# LedController.net
KiCad netlist of a schematic drawn in EAGLE
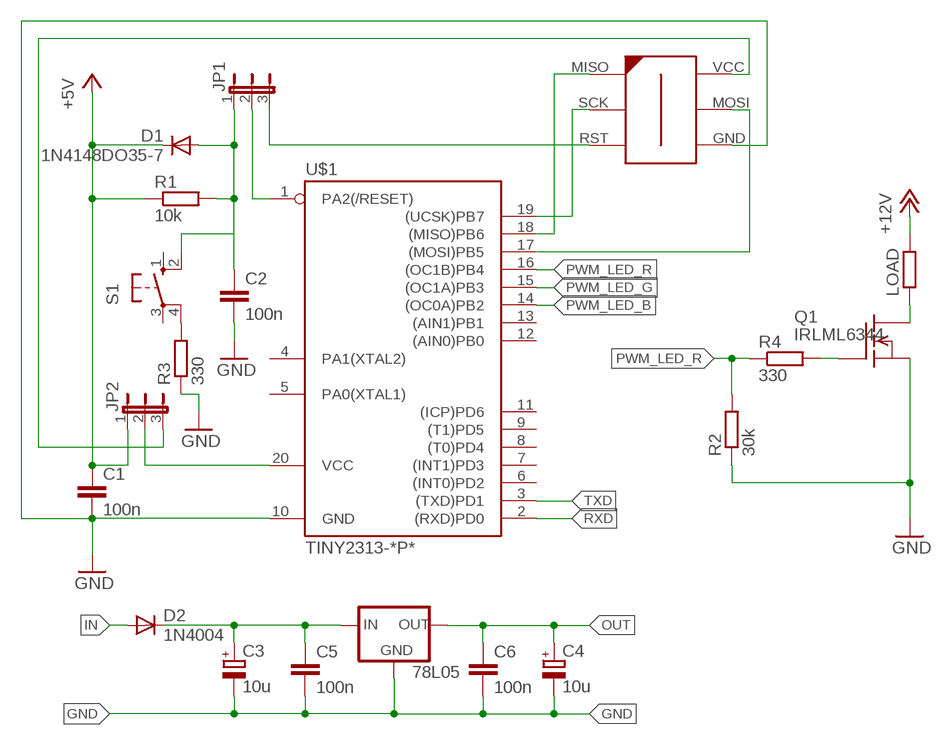
[diagram p0: schematic, sheet 1]

(export (version "E")
  (design (tool "Eeschema 10.0.6"))
  (components
    (comp (ref "78L05")
      (value "78LXX")
      (footprint "eagle-import:78LXX")
      (libsource (lib "eagle-import") (part "78LXX"))
    )
    (comp (ref "C1")
      (value "100n")
      (footprint "eagle-import:C025-024X044")
      (libsource (lib "eagle-import") (part "C-EU025-024X044"))
    )
    (comp (ref "C2")
      (value "100n")
      (footprint "eagle-import:C025-024X044")
      (libsource (lib "eagle-import") (part "C-EU025-024X044"))
    )
    (comp (ref "C3")
      (value "10u")
      (footprint "eagle-import:PANASONIC_A")
      (libsource (lib "eagle-import") (part "CPOL-EUA"))
    )
    (comp (ref "C4")
      (value "10u")
      (footprint "eagle-import:PANASONIC_A")
      (libsource (lib "eagle-import") (part "CPOL-EUA"))
    )
    (comp (ref "C5")
      (value "100n")
      (footprint "eagle-import:C075-032X103")
      (libsource (lib "eagle-import") (part "C-EU075-032X103"))
    )
    (comp (ref "C6")
      (value "100n")
      (footprint "eagle-import:C075-032X103")
      (libsource (lib "eagle-import") (part "C-EU075-032X103"))
    )
    (comp (ref "D1")
      (value "1N4148DO35-7")
      (footprint "eagle-import:DO35-7")
      (libsource (lib "eagle-import") (part "1N4148DO35-7"))
    )
    (comp (ref "D2")
      (value "1N4004")
      (footprint "eagle-import:DO41-10")
      (libsource (lib "eagle-import") (part "1N4004"))
    )
    (comp (ref "JP1")
      (value "JP2E")
      (footprint "eagle-import:JP2")
      (libsource (lib "eagle-import") (part "JP2E"))
    )
    (comp (ref "JP2")
      (value "JP2E")
      (footprint "eagle-import:JP2")
      (libsource (lib "eagle-import") (part "JP2E"))
    )
    (comp (ref "LOAD")
      (value "R-EU_0204/2V")
      (footprint "eagle-import:0204V")
      (libsource (lib "eagle-import") (part "R-EU_0204/2V"))
    )
    (comp (ref "Q1")
      (value "IRLML6344")
      (footprint "eagle-import:TO92")
      (libsource (lib "eagle-import") (part "BSS101"))
    )
    (comp (ref "R1")
      (value "10k")
      (footprint "eagle-import:0204V")
      (libsource (lib "eagle-import") (part "R-EU_0204/2V"))
    )
    (comp (ref "R2")
      (value "30k")
      (footprint "eagle-import:0204V")
      (libsource (lib "eagle-import") (part "R-EU_0204/2V"))
    )
    (comp (ref "R3")
      (value "330")
      (footprint "eagle-import:0204V")
      (libsource (lib "eagle-import") (part "R-EU_0204/2V"))
    )
    (comp (ref "R4")
      (value "330")
      (footprint "eagle-import:0204V")
      (libsource (lib "eagle-import") (part "resistor_R-EU_0204/2V"))
    )
    (comp (ref "S1")
      (value "10-XX")
      (footprint "eagle-import:B3F-10XX")
      (fields (field (name "MPN") "B3F-1000"))
      (libsource (lib "eagle-import") (part "10-XX"))
    )
    (comp (ref "U$1")
      (value "TINY2313-*P*")
      (footprint "eagle-import:DIL20")
      (libsource (lib "eagle-import") (part "TINY2313-P"))
    )
    (comp (ref "U$2")
      (value "AVR-ISP-6-EDGE")
      (footprint "eagle-import:6PAD_ISP")
      (libsource (lib "eagle-import") (part "AVR-ISP-6-EDGE"))
    )
  )
  (nets
    (net (code "1") (name "+5V") (class "Default")
      (node (ref "C1") (pin "1") (pinfunction "1_1") (pintype "passive"))
      (node (ref "D1") (pin "C") (pinfunction "C_C") (pintype "passive"))
      (node (ref "JP2") (pin "1") (pinfunction "1_1") (pintype "passive"))
      (node (ref "R1") (pin "1") (pinfunction "1_1") (pintype "passive"))
    )
    (net (code "2") (name "+12V") (class "Default")
      (node (ref "LOAD") (pin "2") (pinfunction "2_2") (pintype "passive"))
    )
    (net (code "3") (name "GND") (class "Default")
      (node (ref "78L05") (pin "GND") (pinfunction "GND_GND") (pintype "input"))
      (node (ref "C1") (pin "2") (pinfunction "2_2") (pintype "passive"))
      (node (ref "C2") (pin "2") (pinfunction "2_2") (pintype "passive"))
      (node (ref "C3") (pin "-") (pinfunction "-_-") (pintype "passive"))
      (node (ref "C4") (pin "-") (pinfunction "-_-") (pintype "passive"))
      (node (ref "C5") (pin "2") (pinfunction "2_2") (pintype "passive"))
      (node (ref "C6") (pin "2") (pinfunction "2_2") (pintype "passive"))
      (node (ref "Q1") (pin "1") (pinfunction "S_1") (pintype "passive"))
      (node (ref "R2") (pin "1") (pinfunction "1_1") (pintype "passive"))
      (node (ref "R3") (pin "1") (pinfunction "1_1") (pintype "passive"))
      (node (ref "U$1") (pin "10") (pinfunction "GND_10") (pintype "power_in"))
      (node (ref "U$2") (pin "GND") (pinfunction "P$4_GND") (pintype "bidirectional"))
    )
    (net (code "4") (name "IN") (class "Default")
      (node (ref "D2") (pin "A") (pinfunction "A_A") (pintype "passive"))
    )
    (net (code "5") (name "Net-(78L05-PadIN)") (class "Default")
      (node (ref "78L05") (pin "IN") (pinfunction "IN_IN") (pintype "input"))
      (node (ref "C3") (pin "+") (pinfunction "+_+") (pintype "passive"))
      (node (ref "C5") (pin "1") (pinfunction "1_1") (pintype "passive"))
      (node (ref "D2") (pin "C") (pinfunction "C_C") (pintype "passive"))
    )
    (net (code "6") (name "Net-(Q1-D)") (class "Default")
      (node (ref "LOAD") (pin "1") (pinfunction "1_1") (pintype "passive"))
      (node (ref "Q1") (pin "3") (pinfunction "D_3") (pintype "passive"))
    )
    (net (code "7") (name "Net-(Q1-G)") (class "Default")
      (node (ref "Q1") (pin "2") (pinfunction "G_2") (pintype "passive"))
      (node (ref "R4") (pin "2") (pinfunction "2_2") (pintype "passive"))
    )
    (net (code "8") (name "Net-(S1-P1)") (class "Default")
      (node (ref "R3") (pin "2") (pinfunction "2_2") (pintype "passive"))
      (node (ref "S1") (pin "4") (pinfunction "P1_4") (pintype "passive"))
    )
    (net (code "9") (name "Net-(S1-S1)") (class "Default")
      (node (ref "C2") (pin "1") (pinfunction "1_1") (pintype "passive"))
      (node (ref "D1") (pin "A") (pinfunction "A_A") (pintype "passive"))
      (node (ref "JP1") (pin "1") (pinfunction "1_1") (pintype "passive"))
      (node (ref "R1") (pin "2") (pinfunction "2_2") (pintype "passive"))
      (node (ref "S1") (pin "2") (pinfunction "S1_2") (pintype "passive"))
    )
    (net (code "10") (name "Net-(U$1-(MISO)PB6)") (class "Default")
      (node (ref "U$1") (pin "18") (pinfunction "(MISO)PB6_18") (pintype "bidirectional"))
      (node (ref "U$2") (pin "MISO") (pinfunction "P$1_MISO") (pintype "bidirectional"))
    )
    (net (code "11") (name "Net-(U$1-(MOSI)PB5)") (class "Default")
      (node (ref "U$1") (pin "17") (pinfunction "(MOSI)PB5_17") (pintype "bidirectional"))
      (node (ref "U$2") (pin "MOSI") (pinfunction "P$5_MOSI") (pintype "bidirectional"))
    )
    (net (code "12") (name "Net-(U$1-(UCSK)PB7)") (class "Default")
      (node (ref "U$1") (pin "19") (pinfunction "(UCSK)PB7_19") (pintype "bidirectional"))
      (node (ref "U$2") (pin "SCK") (pinfunction "P$2_SCK") (pintype "bidirectional"))
    )
    (net (code "13") (name "Net-(U$1-PA2({slash}RESET))") (class "Default")
      (node (ref "JP1") (pin "2") (pinfunction "2_2") (pintype "passive"))
      (node (ref "U$1") (pin "1") (pinfunction "PA2(/RESET)_1") (pintype "input"))
    )
    (net (code "14") (name "Net-(U$1-VCC)") (class "Default")
      (node (ref "JP2") (pin "2") (pinfunction "2_2") (pintype "passive"))
      (node (ref "U$1") (pin "20") (pinfunction "VCC_20") (pintype "power_in"))
    )
    (net (code "15") (name "Net-(U$2-P$3)") (class "Default")
      (node (ref "JP1") (pin "3") (pinfunction "3_3") (pintype "passive"))
      (node (ref "U$2") (pin "RST") (pinfunction "P$3_RST") (pintype "bidirectional"))
    )
    (net (code "16") (name "Net-(U$2-P$6)") (class "Default")
      (node (ref "JP2") (pin "3") (pinfunction "3_3") (pintype "passive"))
      (node (ref "U$2") (pin "VCC") (pinfunction "P$6_VCC") (pintype "bidirectional"))
    )
    (net (code "17") (name "OUT") (class "Default")
      (node (ref "78L05") (pin "OUT") (pinfunction "OUT_OUT") (pintype "passive"))
      (node (ref "C4") (pin "+") (pinfunction "+_+") (pintype "passive"))
      (node (ref "C6") (pin "1") (pinfunction "1_1") (pintype "passive"))
    )
    (net (code "18") (name "PWM_LED_B") (class "Default")
      (node (ref "U$1") (pin "14") (pinfunction "(OC0A)PB2_14") (pintype "bidirectional"))
    )
    (net (code "19") (name "PWM_LED_G") (class "Default")
      (node (ref "U$1") (pin "15") (pinfunction "(OC1A)PB3_15") (pintype "bidirectional"))
    )
    (net (code "20") (name "PWM_LED_R") (class "Default")
      (node (ref "R2") (pin "2") (pinfunction "2_2") (pintype "passive"))
      (node (ref "R4") (pin "1") (pinfunction "1_1") (pintype "passive"))
      (node (ref "U$1") (pin "16") (pinfunction "(OC1B)PB4_16") (pintype "bidirectional"))
    )
    (net (code "21") (name "RXD") (class "Default")
      (node (ref "U$1") (pin "2") (pinfunction "(RXD)PD0_2") (pintype "bidirectional"))
    )
    (net (code "22") (name "TXD") (class "Default")
      (node (ref "U$1") (pin "3") (pinfunction "(TXD)PD1_3") (pintype "bidirectional"))
    )
    (net (code "23") (name "unconnected-(S1-P-Pad3)") (class "Default")
      (node (ref "S1") (pin "3") (pinfunction "P_3") (pintype "passive"))
    )
    (net (code "24") (name "unconnected-(S1-S-Pad1)") (class "Default")
      (node (ref "S1") (pin "1") (pinfunction "S_1") (pintype "passive"))
    )
    (net (code "25") (name "unconnected-(U$1-(AIN0)PB0-Pad12)") (class "Default")
      (node (ref "U$1") (pin "12") (pinfunction "(AIN0)PB0_12") (pintype "bidirectional"))
    )
    (net (code "26") (name "unconnected-(U$1-(AIN1)PB1-Pad13)") (class "Default")
      (node (ref "U$1") (pin "13") (pinfunction "(AIN1)PB1_13") (pintype "bidirectional"))
    )
    (net (code "27") (name "unconnected-(U$1-(ICP)PD6-Pad11)") (class "Default")
      (node (ref "U$1") (pin "11") (pinfunction "(ICP)PD6_11") (pintype "bidirectional"))
    )
    (net (code "28") (name "unconnected-(U$1-(INT0)PD2-Pad6)") (class "Default")
      (node (ref "U$1") (pin "6") (pinfunction "(INT0)PD2_6") (pintype "bidirectional"))
    )
    (net (code "29") (name "unconnected-(U$1-(INT1)PD3-Pad7)") (class "Default")
      (node (ref "U$1") (pin "7") (pinfunction "(INT1)PD3_7") (pintype "bidirectional"))
    )
    (net (code "30") (name "unconnected-(U$1-(T0)PD4-Pad8)") (class "Default")
      (node (ref "U$1") (pin "8") (pinfunction "(T0)PD4_8") (pintype "bidirectional"))
    )
    (net (code "31") (name "unconnected-(U$1-(T1)PD5-Pad9)") (class "Default")
      (node (ref "U$1") (pin "9") (pinfunction "(T1)PD5_9") (pintype "bidirectional"))
    )
    (net (code "32") (name "unconnected-(U$1-PA0(XTAL1)-Pad5)") (class "Default")
      (node (ref "U$1") (pin "5") (pinfunction "PA0(XTAL1)_5") (pintype "bidirectional"))
    )
    (net (code "33") (name "unconnected-(U$1-PA1(XTAL2)-Pad4)") (class "Default")
      (node (ref "U$1") (pin "4") (pinfunction "PA1(XTAL2)_4") (pintype "bidirectional"))
    )
  )
)
